# Callisto_Teknic_MSO_PBx4_v1p1.net
KiCad netlist of a schematic drawn in EAGLE
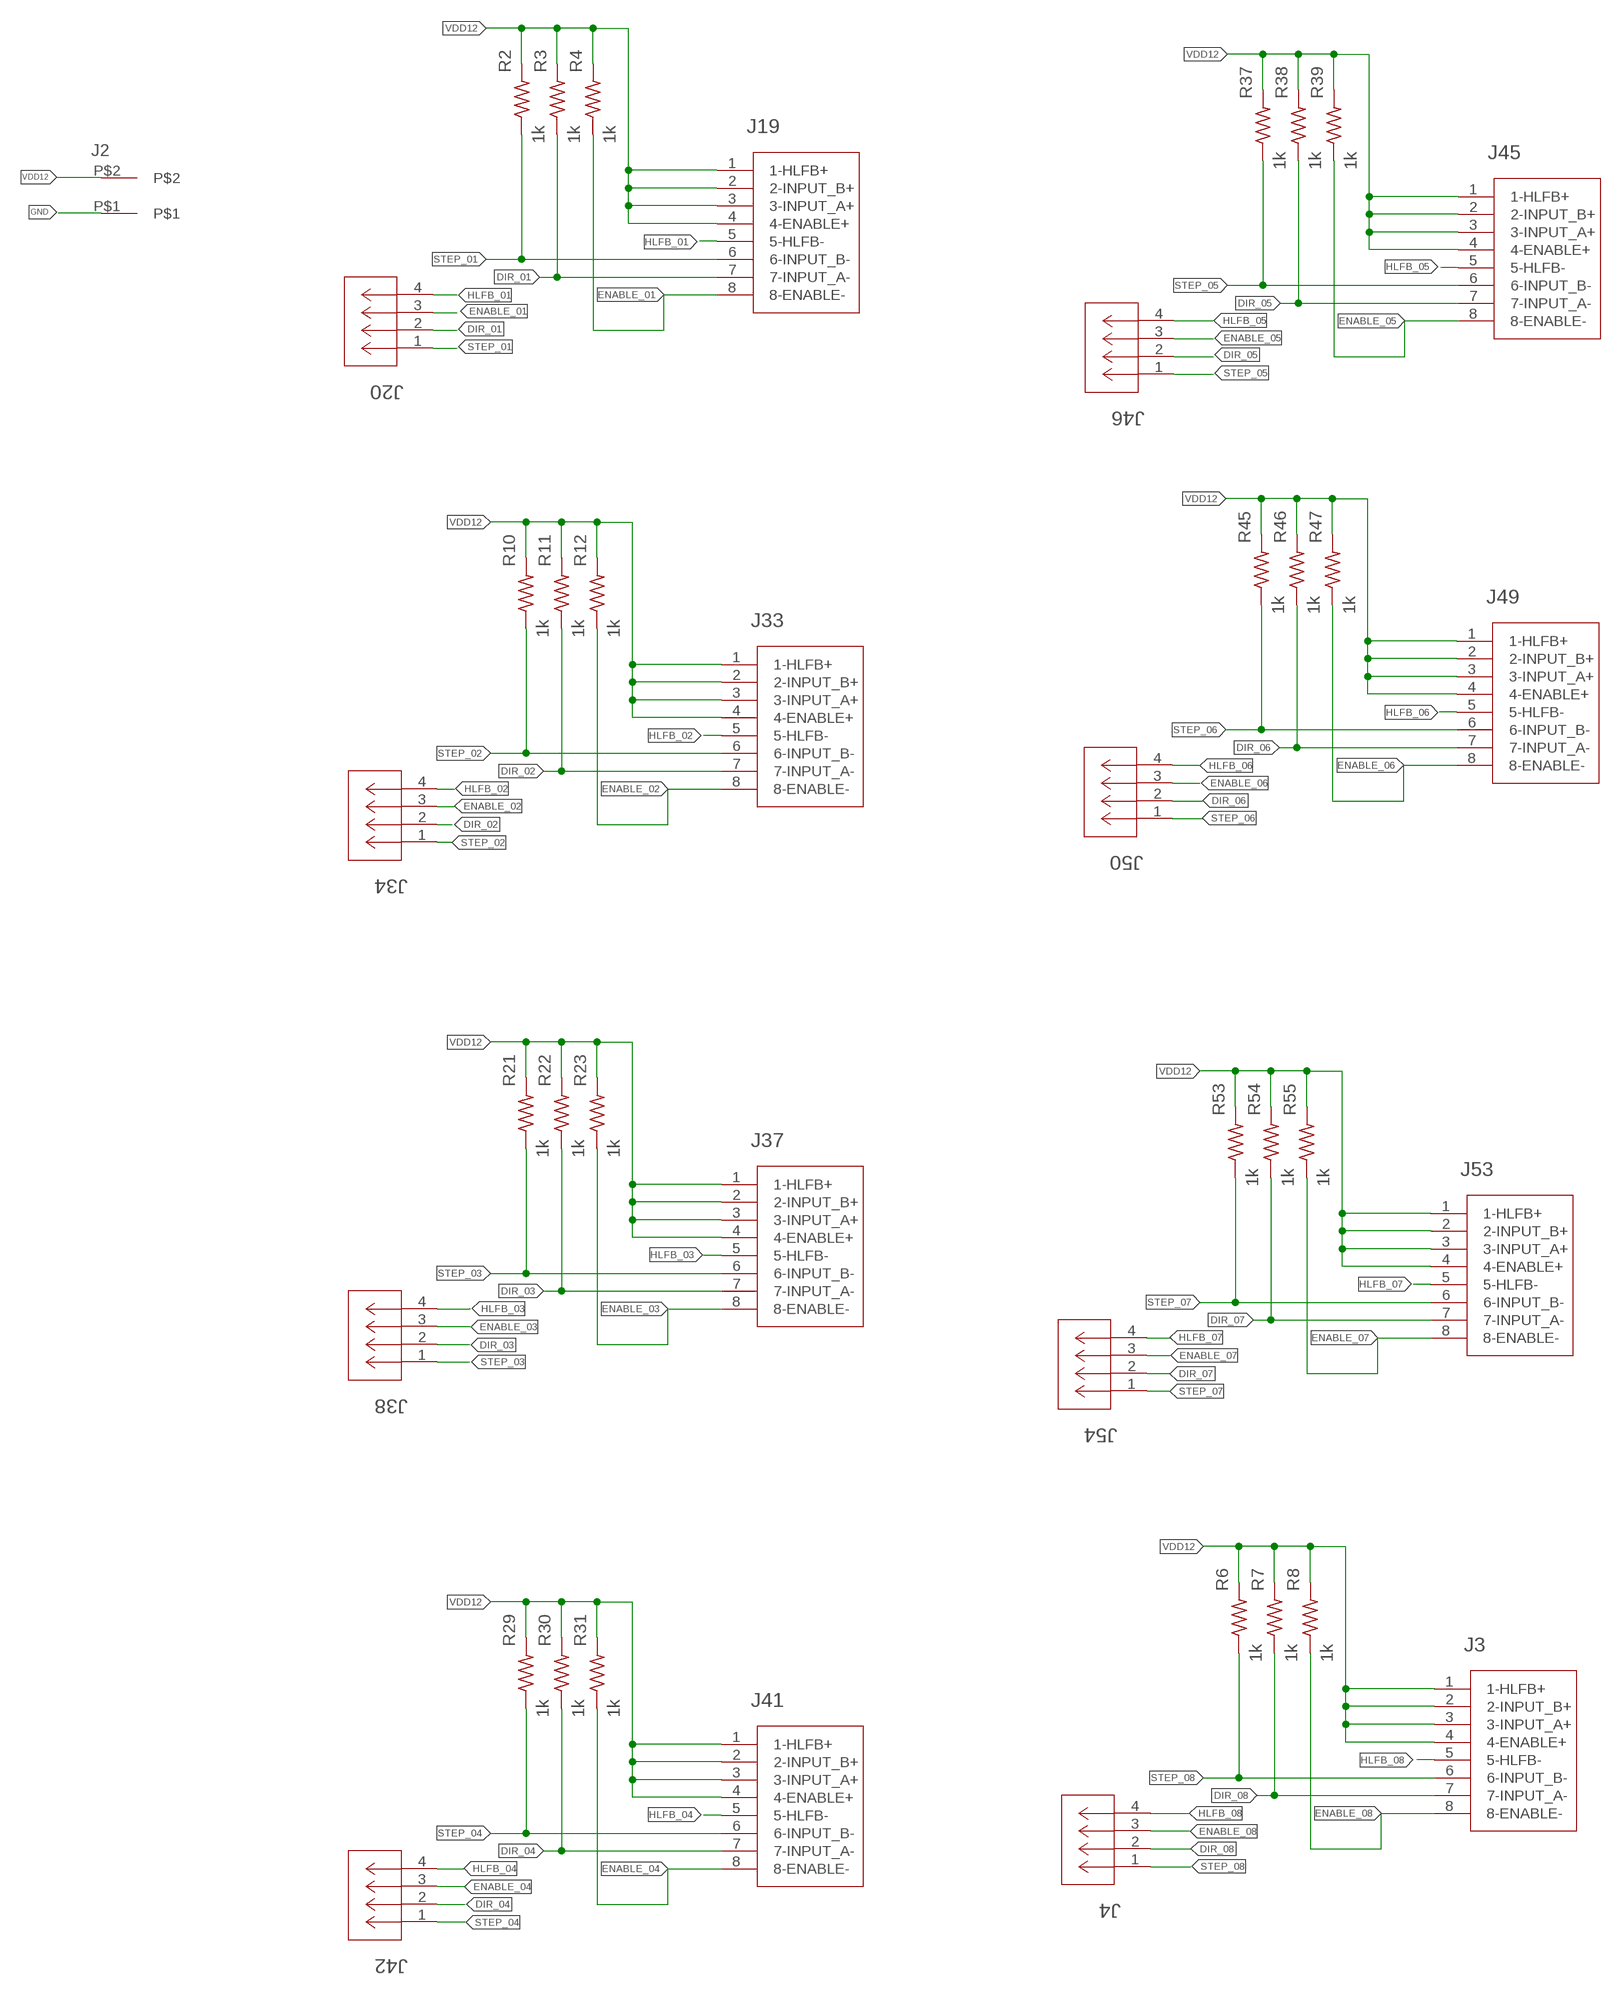
[diagram p0: schematic, sheet 1]

(export (version "E")
  (design (tool "Eeschema 10.0.6"))
  (components
    (comp (ref "J2")
      (value "2-pos")
      (footprint "eagle-import:2_3.81MM_PITCH")
      (fields (field (name "PARTNO") "691322310002"))
      (libsource (lib "eagle-import") (part "3.81MM_1_X_2_RT_ANGLE_PLUG_HEADER"))
    )
    (comp (ref "J3")
      (value "TEKNIC_8PIN_MOTOR")
      (footprint "eagle-import:CON_39281083")
      (fields
        (field (name "MANUFACTURER_PART_NUMBER") "39281083")
        (field (name "COPYRIGHT") "Copyright (C) 2022 Ultra Librarian. All rights reserved.")
      )
      (libsource (lib "eagle-import") (part "TEKNIC_8PIN_MOTOR"))
    )
    (comp (ref "J4")
      (value "CONN_530470410_PICOBLADE_X_4")
      (footprint "eagle-import:CON_530470410_MOL")
      (fields
        (field (name "MANUFACTURER_PART_NUMBER") "530470410")
        (field (name "COPYRIGHT") "Copyright (C) 2022 Ultra Librarian. All rights reserved.")
      )
      (libsource (lib "eagle-import") (part "CONN_530470410_PICOBLADE_X_4"))
    )
    (comp (ref "J19")
      (value "TEKNIC_8PIN_MOTOR")
      (footprint "eagle-import:CON_39281083")
      (fields
        (field (name "MANUFACTURER_PART_NUMBER") "39281083")
        (field (name "COPYRIGHT") "Copyright (C) 2022 Ultra Librarian. All rights reserved.")
      )
      (libsource (lib "eagle-import") (part "TEKNIC_8PIN_MOTOR"))
    )
    (comp (ref "J20")
      (value "CONN_530470410_PICOBLADE_X_4")
      (footprint "eagle-import:CON_530470410_MOL")
      (fields
        (field (name "MANUFACTURER_PART_NUMBER") "530470410")
        (field (name "COPYRIGHT") "Copyright (C) 2022 Ultra Librarian. All rights reserved.")
      )
      (libsource (lib "eagle-import") (part "CONN_530470410_PICOBLADE_X_4"))
    )
    (comp (ref "J33")
      (value "TEKNIC_8PIN_MOTOR")
      (footprint "eagle-import:CON_39281083")
      (fields
        (field (name "MANUFACTURER_PART_NUMBER") "39281083")
        (field (name "COPYRIGHT") "Copyright (C) 2022 Ultra Librarian. All rights reserved.")
      )
      (libsource (lib "eagle-import") (part "TEKNIC_8PIN_MOTOR"))
    )
    (comp (ref "J34")
      (value "CONN_530470410_PICOBLADE_X_4")
      (footprint "eagle-import:CON_530470410_MOL")
      (fields
        (field (name "MANUFACTURER_PART_NUMBER") "530470410")
        (field (name "COPYRIGHT") "Copyright (C) 2022 Ultra Librarian. All rights reserved.")
      )
      (libsource (lib "eagle-import") (part "CONN_530470410_PICOBLADE_X_4"))
    )
    (comp (ref "J37")
      (value "TEKNIC_8PIN_MOTOR")
      (footprint "eagle-import:CON_39281083")
      (fields
        (field (name "MANUFACTURER_PART_NUMBER") "39281083")
        (field (name "COPYRIGHT") "Copyright (C) 2022 Ultra Librarian. All rights reserved.")
      )
      (libsource (lib "eagle-import") (part "TEKNIC_8PIN_MOTOR"))
    )
    (comp (ref "J38")
      (value "CONN_530470410_PICOBLADE_X_4")
      (footprint "eagle-import:CON_530470410_MOL")
      (fields
        (field (name "MANUFACTURER_PART_NUMBER") "530470410")
        (field (name "COPYRIGHT") "Copyright (C) 2022 Ultra Librarian. All rights reserved.")
      )
      (libsource (lib "eagle-import") (part "CONN_530470410_PICOBLADE_X_4"))
    )
    (comp (ref "J41")
      (value "TEKNIC_8PIN_MOTOR")
      (footprint "eagle-import:CON_39281083")
      (fields
        (field (name "MANUFACTURER_PART_NUMBER") "39281083")
        (field (name "COPYRIGHT") "Copyright (C) 2022 Ultra Librarian. All rights reserved.")
      )
      (libsource (lib "eagle-import") (part "TEKNIC_8PIN_MOTOR"))
    )
    (comp (ref "J42")
      (value "CONN_530470410_PICOBLADE_X_4")
      (footprint "eagle-import:CON_530470410_MOL")
      (fields
        (field (name "MANUFACTURER_PART_NUMBER") "530470410")
        (field (name "COPYRIGHT") "Copyright (C) 2022 Ultra Librarian. All rights reserved.")
      )
      (libsource (lib "eagle-import") (part "CONN_530470410_PICOBLADE_X_4"))
    )
    (comp (ref "J45")
      (value "TEKNIC_8PIN_MOTOR")
      (footprint "eagle-import:CON_39281083")
      (fields
        (field (name "MANUFACTURER_PART_NUMBER") "39281083")
        (field (name "COPYRIGHT") "Copyright (C) 2022 Ultra Librarian. All rights reserved.")
      )
      (libsource (lib "eagle-import") (part "TEKNIC_8PIN_MOTOR"))
    )
    (comp (ref "J46")
      (value "CONN_530470410_PICOBLADE_X_4")
      (footprint "eagle-import:CON_530470410_MOL")
      (fields
        (field (name "MANUFACTURER_PART_NUMBER") "530470410")
        (field (name "COPYRIGHT") "Copyright (C) 2022 Ultra Librarian. All rights reserved.")
      )
      (libsource (lib "eagle-import") (part "CONN_530470410_PICOBLADE_X_4"))
    )
    (comp (ref "J49")
      (value "TEKNIC_8PIN_MOTOR")
      (footprint "eagle-import:CON_39281083")
      (fields
        (field (name "MANUFACTURER_PART_NUMBER") "39281083")
        (field (name "COPYRIGHT") "Copyright (C) 2022 Ultra Librarian. All rights reserved.")
      )
      (libsource (lib "eagle-import") (part "TEKNIC_8PIN_MOTOR"))
    )
    (comp (ref "J50")
      (value "CONN_530470410_PICOBLADE_X_4")
      (footprint "eagle-import:CON_530470410_MOL")
      (fields
        (field (name "MANUFACTURER_PART_NUMBER") "530470410")
        (field (name "COPYRIGHT") "Copyright (C) 2022 Ultra Librarian. All rights reserved.")
      )
      (libsource (lib "eagle-import") (part "CONN_530470410_PICOBLADE_X_4"))
    )
    (comp (ref "J53")
      (value "TEKNIC_8PIN_MOTOR")
      (footprint "eagle-import:CON_39281083")
      (fields
        (field (name "MANUFACTURER_PART_NUMBER") "39281083")
        (field (name "COPYRIGHT") "Copyright (C) 2022 Ultra Librarian. All rights reserved.")
      )
      (libsource (lib "eagle-import") (part "TEKNIC_8PIN_MOTOR"))
    )
    (comp (ref "J54")
      (value "CONN_530470410_PICOBLADE_X_4")
      (footprint "eagle-import:CON_530470410_MOL")
      (fields
        (field (name "MANUFACTURER_PART_NUMBER") "530470410")
        (field (name "COPYRIGHT") "Copyright (C) 2022 Ultra Librarian. All rights reserved.")
      )
      (libsource (lib "eagle-import") (part "CONN_530470410_PICOBLADE_X_4"))
    )
    (comp (ref "R2")
      (value "1k")
      (footprint "eagle-import:0805")
      (libsource (lib "eagle-import") (part "R_0805"))
    )
    (comp (ref "R3")
      (value "1k")
      (footprint "eagle-import:0805")
      (libsource (lib "eagle-import") (part "R_0805"))
    )
    (comp (ref "R4")
      (value "1k")
      (footprint "eagle-import:0805")
      (libsource (lib "eagle-import") (part "R_0805"))
    )
    (comp (ref "R6")
      (value "1k")
      (footprint "eagle-import:0805")
      (libsource (lib "eagle-import") (part "R_0805"))
    )
    (comp (ref "R7")
      (value "1k")
      (footprint "eagle-import:0805")
      (libsource (lib "eagle-import") (part "R_0805"))
    )
    (comp (ref "R8")
      (value "1k")
      (footprint "eagle-import:0805")
      (libsource (lib "eagle-import") (part "R_0805"))
    )
    (comp (ref "R10")
      (value "1k")
      (footprint "eagle-import:0805")
      (libsource (lib "eagle-import") (part "R_0805"))
    )
    (comp (ref "R11")
      (value "1k")
      (footprint "eagle-import:0805")
      (libsource (lib "eagle-import") (part "R_0805"))
    )
    (comp (ref "R12")
      (value "1k")
      (footprint "eagle-import:0805")
      (libsource (lib "eagle-import") (part "R_0805"))
    )
    (comp (ref "R21")
      (value "1k")
      (footprint "eagle-import:0805")
      (libsource (lib "eagle-import") (part "R_0805"))
    )
    (comp (ref "R22")
      (value "1k")
      (footprint "eagle-import:0805")
      (libsource (lib "eagle-import") (part "R_0805"))
    )
    (comp (ref "R23")
      (value "1k")
      (footprint "eagle-import:0805")
      (libsource (lib "eagle-import") (part "R_0805"))
    )
    (comp (ref "R29")
      (value "1k")
      (footprint "eagle-import:0805")
      (libsource (lib "eagle-import") (part "R_0805"))
    )
    (comp (ref "R30")
      (value "1k")
      (footprint "eagle-import:0805")
      (libsource (lib "eagle-import") (part "R_0805"))
    )
    (comp (ref "R31")
      (value "1k")
      (footprint "eagle-import:0805")
      (libsource (lib "eagle-import") (part "R_0805"))
    )
    (comp (ref "R37")
      (value "1k")
      (footprint "eagle-import:0805")
      (libsource (lib "eagle-import") (part "R_0805"))
    )
    (comp (ref "R38")
      (value "1k")
      (footprint "eagle-import:0805")
      (libsource (lib "eagle-import") (part "R_0805"))
    )
    (comp (ref "R39")
      (value "1k")
      (footprint "eagle-import:0805")
      (libsource (lib "eagle-import") (part "R_0805"))
    )
    (comp (ref "R45")
      (value "1k")
      (footprint "eagle-import:0805")
      (libsource (lib "eagle-import") (part "R_0805"))
    )
    (comp (ref "R46")
      (value "1k")
      (footprint "eagle-import:0805")
      (libsource (lib "eagle-import") (part "R_0805"))
    )
    (comp (ref "R47")
      (value "1k")
      (footprint "eagle-import:0805")
      (libsource (lib "eagle-import") (part "R_0805"))
    )
    (comp (ref "R53")
      (value "1k")
      (footprint "eagle-import:0805")
      (libsource (lib "eagle-import") (part "R_0805"))
    )
    (comp (ref "R54")
      (value "1k")
      (footprint "eagle-import:0805")
      (libsource (lib "eagle-import") (part "R_0805"))
    )
    (comp (ref "R55")
      (value "1k")
      (footprint "eagle-import:0805")
      (libsource (lib "eagle-import") (part "R_0805"))
    )
  )
  (nets
    (net (code "1") (name "DIR_01") (class "Default")
      (node (ref "J19") (pin "7") (pinfunction "7-INPUT_A-_7") (pintype "passive"))
      (node (ref "J20") (pin "2") (pinfunction "2_2") (pintype "passive"))
      (node (ref "R3") (pin "1") (pinfunction "1_1") (pintype "passive"))
    )
    (net (code "2") (name "DIR_02") (class "Default")
      (node (ref "J33") (pin "7") (pinfunction "7-INPUT_A-_7") (pintype "passive"))
      (node (ref "J34") (pin "2") (pinfunction "2_2") (pintype "passive"))
      (node (ref "R11") (pin "1") (pinfunction "1_1") (pintype "passive"))
    )
    (net (code "3") (name "DIR_03") (class "Default")
      (node (ref "J37") (pin "7") (pinfunction "7-INPUT_A-_7") (pintype "passive"))
      (node (ref "J38") (pin "2") (pinfunction "2_2") (pintype "passive"))
      (node (ref "R22") (pin "1") (pinfunction "1_1") (pintype "passive"))
    )
    (net (code "4") (name "DIR_04") (class "Default")
      (node (ref "J41") (pin "7") (pinfunction "7-INPUT_A-_7") (pintype "passive"))
      (node (ref "J42") (pin "2") (pinfunction "2_2") (pintype "passive"))
      (node (ref "R30") (pin "1") (pinfunction "1_1") (pintype "passive"))
    )
    (net (code "5") (name "DIR_05") (class "Default")
      (node (ref "J45") (pin "7") (pinfunction "7-INPUT_A-_7") (pintype "passive"))
      (node (ref "J46") (pin "2") (pinfunction "2_2") (pintype "passive"))
      (node (ref "R38") (pin "1") (pinfunction "1_1") (pintype "passive"))
    )
    (net (code "6") (name "DIR_06") (class "Default")
      (node (ref "J49") (pin "7") (pinfunction "7-INPUT_A-_7") (pintype "passive"))
      (node (ref "J50") (pin "2") (pinfunction "2_2") (pintype "passive"))
      (node (ref "R46") (pin "1") (pinfunction "1_1") (pintype "passive"))
    )
    (net (code "7") (name "DIR_07") (class "Default")
      (node (ref "J53") (pin "7") (pinfunction "7-INPUT_A-_7") (pintype "passive"))
      (node (ref "J54") (pin "2") (pinfunction "2_2") (pintype "passive"))
      (node (ref "R54") (pin "1") (pinfunction "1_1") (pintype "passive"))
    )
    (net (code "8") (name "DIR_08") (class "Default")
      (node (ref "J3") (pin "7") (pinfunction "7-INPUT_A-_7") (pintype "passive"))
      (node (ref "J4") (pin "2") (pinfunction "2_2") (pintype "passive"))
      (node (ref "R7") (pin "1") (pinfunction "1_1") (pintype "passive"))
    )
    (net (code "9") (name "ENABLE_01") (class "Default")
      (node (ref "J19") (pin "8") (pinfunction "8-ENABLE-_8") (pintype "passive"))
      (node (ref "J20") (pin "3") (pinfunction "3_3") (pintype "passive"))
      (node (ref "R4") (pin "1") (pinfunction "1_1") (pintype "passive"))
    )
    (net (code "10") (name "ENABLE_02") (class "Default")
      (node (ref "J33") (pin "8") (pinfunction "8-ENABLE-_8") (pintype "passive"))
      (node (ref "J34") (pin "3") (pinfunction "3_3") (pintype "passive"))
      (node (ref "R12") (pin "1") (pinfunction "1_1") (pintype "passive"))
    )
    (net (code "11") (name "ENABLE_03") (class "Default")
      (node (ref "J37") (pin "8") (pinfunction "8-ENABLE-_8") (pintype "passive"))
      (node (ref "J38") (pin "3") (pinfunction "3_3") (pintype "passive"))
      (node (ref "R23") (pin "1") (pinfunction "1_1") (pintype "passive"))
    )
    (net (code "12") (name "ENABLE_04") (class "Default")
      (node (ref "J41") (pin "8") (pinfunction "8-ENABLE-_8") (pintype "passive"))
      (node (ref "J42") (pin "3") (pinfunction "3_3") (pintype "passive"))
      (node (ref "R31") (pin "1") (pinfunction "1_1") (pintype "passive"))
    )
    (net (code "13") (name "ENABLE_05") (class "Default")
      (node (ref "J45") (pin "8") (pinfunction "8-ENABLE-_8") (pintype "passive"))
      (node (ref "J46") (pin "3") (pinfunction "3_3") (pintype "passive"))
      (node (ref "R39") (pin "1") (pinfunction "1_1") (pintype "passive"))
    )
    (net (code "14") (name "ENABLE_06") (class "Default")
      (node (ref "J49") (pin "8") (pinfunction "8-ENABLE-_8") (pintype "passive"))
      (node (ref "J50") (pin "3") (pinfunction "3_3") (pintype "passive"))
      (node (ref "R47") (pin "1") (pinfunction "1_1") (pintype "passive"))
    )
    (net (code "15") (name "ENABLE_07") (class "Default")
      (node (ref "J53") (pin "8") (pinfunction "8-ENABLE-_8") (pintype "passive"))
      (node (ref "J54") (pin "3") (pinfunction "3_3") (pintype "passive"))
      (node (ref "R55") (pin "1") (pinfunction "1_1") (pintype "passive"))
    )
    (net (code "16") (name "ENABLE_08") (class "Default")
      (node (ref "J3") (pin "8") (pinfunction "8-ENABLE-_8") (pintype "passive"))
      (node (ref "J4") (pin "3") (pinfunction "3_3") (pintype "passive"))
      (node (ref "R8") (pin "1") (pinfunction "1_1") (pintype "passive"))
    )
    (net (code "17") (name "GND") (class "Default")
      (node (ref "J2") (pin "P$1") (pinfunction "P$1_P$1") (pintype "bidirectional"))
    )
    (net (code "18") (name "HLFB_01") (class "Default")
      (node (ref "J19") (pin "5") (pinfunction "5-HLFB-_5") (pintype "passive"))
      (node (ref "J20") (pin "4") (pinfunction "4_4") (pintype "passive"))
    )
    (net (code "19") (name "HLFB_02") (class "Default")
      (node (ref "J33") (pin "5") (pinfunction "5-HLFB-_5") (pintype "passive"))
      (node (ref "J34") (pin "4") (pinfunction "4_4") (pintype "passive"))
    )
    (net (code "20") (name "HLFB_03") (class "Default")
      (node (ref "J37") (pin "5") (pinfunction "5-HLFB-_5") (pintype "passive"))
      (node (ref "J38") (pin "4") (pinfunction "4_4") (pintype "passive"))
    )
    (net (code "21") (name "HLFB_04") (class "Default")
      (node (ref "J41") (pin "5") (pinfunction "5-HLFB-_5") (pintype "passive"))
      (node (ref "J42") (pin "4") (pinfunction "4_4") (pintype "passive"))
    )
    (net (code "22") (name "HLFB_05") (class "Default")
      (node (ref "J45") (pin "5") (pinfunction "5-HLFB-_5") (pintype "passive"))
      (node (ref "J46") (pin "4") (pinfunction "4_4") (pintype "passive"))
    )
    (net (code "23") (name "HLFB_06") (class "Default")
      (node (ref "J49") (pin "5") (pinfunction "5-HLFB-_5") (pintype "passive"))
      (node (ref "J50") (pin "4") (pinfunction "4_4") (pintype "passive"))
    )
    (net (code "24") (name "HLFB_07") (class "Default")
      (node (ref "J53") (pin "5") (pinfunction "5-HLFB-_5") (pintype "passive"))
      (node (ref "J54") (pin "4") (pinfunction "4_4") (pintype "passive"))
    )
    (net (code "25") (name "HLFB_08") (class "Default")
      (node (ref "J3") (pin "5") (pinfunction "5-HLFB-_5") (pintype "passive"))
      (node (ref "J4") (pin "4") (pinfunction "4_4") (pintype "passive"))
    )
    (net (code "26") (name "STEP_01") (class "Default")
      (node (ref "J19") (pin "6") (pinfunction "6-INPUT_B-_6") (pintype "passive"))
      (node (ref "J20") (pin "1") (pinfunction "1_1") (pintype "passive"))
      (node (ref "R2") (pin "1") (pinfunction "1_1") (pintype "passive"))
    )
    (net (code "27") (name "STEP_02") (class "Default")
      (node (ref "J33") (pin "6") (pinfunction "6-INPUT_B-_6") (pintype "passive"))
      (node (ref "J34") (pin "1") (pinfunction "1_1") (pintype "passive"))
      (node (ref "R10") (pin "1") (pinfunction "1_1") (pintype "passive"))
    )
    (net (code "28") (name "STEP_03") (class "Default")
      (node (ref "J37") (pin "6") (pinfunction "6-INPUT_B-_6") (pintype "passive"))
      (node (ref "J38") (pin "1") (pinfunction "1_1") (pintype "passive"))
      (node (ref "R21") (pin "1") (pinfunction "1_1") (pintype "passive"))
    )
    (net (code "29") (name "STEP_04") (class "Default")
      (node (ref "J41") (pin "6") (pinfunction "6-INPUT_B-_6") (pintype "passive"))
      (node (ref "J42") (pin "1") (pinfunction "1_1") (pintype "passive"))
      (node (ref "R29") (pin "1") (pinfunction "1_1") (pintype "passive"))
    )
    (net (code "30") (name "STEP_05") (class "Default")
      (node (ref "J45") (pin "6") (pinfunction "6-INPUT_B-_6") (pintype "passive"))
      (node (ref "J46") (pin "1") (pinfunction "1_1") (pintype "passive"))
      (node (ref "R37") (pin "1") (pinfunction "1_1") (pintype "passive"))
    )
    (net (code "31") (name "STEP_06") (class "Default")
      (node (ref "J49") (pin "6") (pinfunction "6-INPUT_B-_6") (pintype "passive"))
      (node (ref "J50") (pin "1") (pinfunction "1_1") (pintype "passive"))
      (node (ref "R45") (pin "1") (pinfunction "1_1") (pintype "passive"))
    )
    (net (code "32") (name "STEP_07") (class "Default")
      (node (ref "J53") (pin "6") (pinfunction "6-INPUT_B-_6") (pintype "passive"))
      (node (ref "J54") (pin "1") (pinfunction "1_1") (pintype "passive"))
      (node (ref "R53") (pin "1") (pinfunction "1_1") (pintype "passive"))
    )
    (net (code "33") (name "STEP_08") (class "Default")
      (node (ref "J3") (pin "6") (pinfunction "6-INPUT_B-_6") (pintype "passive"))
      (node (ref "J4") (pin "1") (pinfunction "1_1") (pintype "passive"))
      (node (ref "R6") (pin "1") (pinfunction "1_1") (pintype "passive"))
    )
    (net (code "34") (name "VDD12") (class "Default")
      (node (ref "J19") (pin "1") (pinfunction "1-HLFB+_1") (pintype "passive"))
      (node (ref "J19") (pin "2") (pinfunction "2-INPUT_B+_2") (pintype "passive"))
      (node (ref "J19") (pin "3") (pinfunction "3-INPUT_A+_3") (pintype "passive"))
      (node (ref "J19") (pin "4") (pinfunction "4-ENABLE+_4") (pintype "passive"))
      (node (ref "J2") (pin "P$2") (pinfunction "P$2_P$2") (pintype "bidirectional"))
      (node (ref "J3") (pin "1") (pinfunction "1-HLFB+_1") (pintype "passive"))
      (node (ref "J3") (pin "2") (pinfunction "2-INPUT_B+_2") (pintype "passive"))
      (node (ref "J3") (pin "3") (pinfunction "3-INPUT_A+_3") (pintype "passive"))
      (node (ref "J3") (pin "4") (pinfunction "4-ENABLE+_4") (pintype "passive"))
      (node (ref "J33") (pin "1") (pinfunction "1-HLFB+_1") (pintype "passive"))
      (node (ref "J33") (pin "2") (pinfunction "2-INPUT_B+_2") (pintype "passive"))
      (node (ref "J33") (pin "3") (pinfunction "3-INPUT_A+_3") (pintype "passive"))
      (node (ref "J33") (pin "4") (pinfunction "4-ENABLE+_4") (pintype "passive"))
      (node (ref "J37") (pin "1") (pinfunction "1-HLFB+_1") (pintype "passive"))
      (node (ref "J37") (pin "2") (pinfunction "2-INPUT_B+_2") (pintype "passive"))
      (node (ref "J37") (pin "3") (pinfunction "3-INPUT_A+_3") (pintype "passive"))
      (node (ref "J37") (pin "4") (pinfunction "4-ENABLE+_4") (pintype "passive"))
      (node (ref "J41") (pin "1") (pinfunction "1-HLFB+_1") (pintype "passive"))
      (node (ref "J41") (pin "2") (pinfunction "2-INPUT_B+_2") (pintype "passive"))
      (node (ref "J41") (pin "3") (pinfunction "3-INPUT_A+_3") (pintype "passive"))
      (node (ref "J41") (pin "4") (pinfunction "4-ENABLE+_4") (pintype "passive"))
      (node (ref "J45") (pin "1") (pinfunction "1-HLFB+_1") (pintype "passive"))
      (node (ref "J45") (pin "2") (pinfunction "2-INPUT_B+_2") (pintype "passive"))
      (node (ref "J45") (pin "3") (pinfunction "3-INPUT_A+_3") (pintype "passive"))
      (node (ref "J45") (pin "4") (pinfunction "4-ENABLE+_4") (pintype "passive"))
      (node (ref "J49") (pin "1") (pinfunction "1-HLFB+_1") (pintype "passive"))
      (node (ref "J49") (pin "2") (pinfunction "2-INPUT_B+_2") (pintype "passive"))
      (node (ref "J49") (pin "3") (pinfunction "3-INPUT_A+_3") (pintype "passive"))
      (node (ref "J49") (pin "4") (pinfunction "4-ENABLE+_4") (pintype "passive"))
      (node (ref "J53") (pin "1") (pinfunction "1-HLFB+_1") (pintype "passive"))
      (node (ref "J53") (pin "2") (pinfunction "2-INPUT_B+_2") (pintype "passive"))
      (node (ref "J53") (pin "3") (pinfunction "3-INPUT_A+_3") (pintype "passive"))
      (node (ref "J53") (pin "4") (pinfunction "4-ENABLE+_4") (pintype "passive"))
      (node (ref "R10") (pin "2") (pinfunction "2_2") (pintype "passive"))
      (node (ref "R11") (pin "2") (pinfunction "2_2") (pintype "passive"))
      (node (ref "R12") (pin "2") (pinfunction "2_2") (pintype "passive"))
      (node (ref "R2") (pin "2") (pinfunction "2_2") (pintype "passive"))
      (node (ref "R21") (pin "2") (pinfunction "2_2") (pintype "passive"))
      (node (ref "R22") (pin "2") (pinfunction "2_2") (pintype "passive"))
      (node (ref "R23") (pin "2") (pinfunction "2_2") (pintype "passive"))
      (node (ref "R29") (pin "2") (pinfunction "2_2") (pintype "passive"))
      (node (ref "R3") (pin "2") (pinfunction "2_2") (pintype "passive"))
      (node (ref "R30") (pin "2") (pinfunction "2_2") (pintype "passive"))
      (node (ref "R31") (pin "2") (pinfunction "2_2") (pintype "passive"))
      (node (ref "R37") (pin "2") (pinfunction "2_2") (pintype "passive"))
      (node (ref "R38") (pin "2") (pinfunction "2_2") (pintype "passive"))
      (node (ref "R39") (pin "2") (pinfunction "2_2") (pintype "passive"))
      (node (ref "R4") (pin "2") (pinfunction "2_2") (pintype "passive"))
      (node (ref "R45") (pin "2") (pinfunction "2_2") (pintype "passive"))
      (node (ref "R46") (pin "2") (pinfunction "2_2") (pintype "passive"))
      (node (ref "R47") (pin "2") (pinfunction "2_2") (pintype "passive"))
      (node (ref "R53") (pin "2") (pinfunction "2_2") (pintype "passive"))
      (node (ref "R54") (pin "2") (pinfunction "2_2") (pintype "passive"))
      (node (ref "R55") (pin "2") (pinfunction "2_2") (pintype "passive"))
      (node (ref "R6") (pin "2") (pinfunction "2_2") (pintype "passive"))
      (node (ref "R7") (pin "2") (pinfunction "2_2") (pintype "passive"))
      (node (ref "R8") (pin "2") (pinfunction "2_2") (pintype "passive"))
    )
  )
)
